# FPGA_Banks_DDR3.net
KiCad netlist of a schematic drawn in Altium Designer
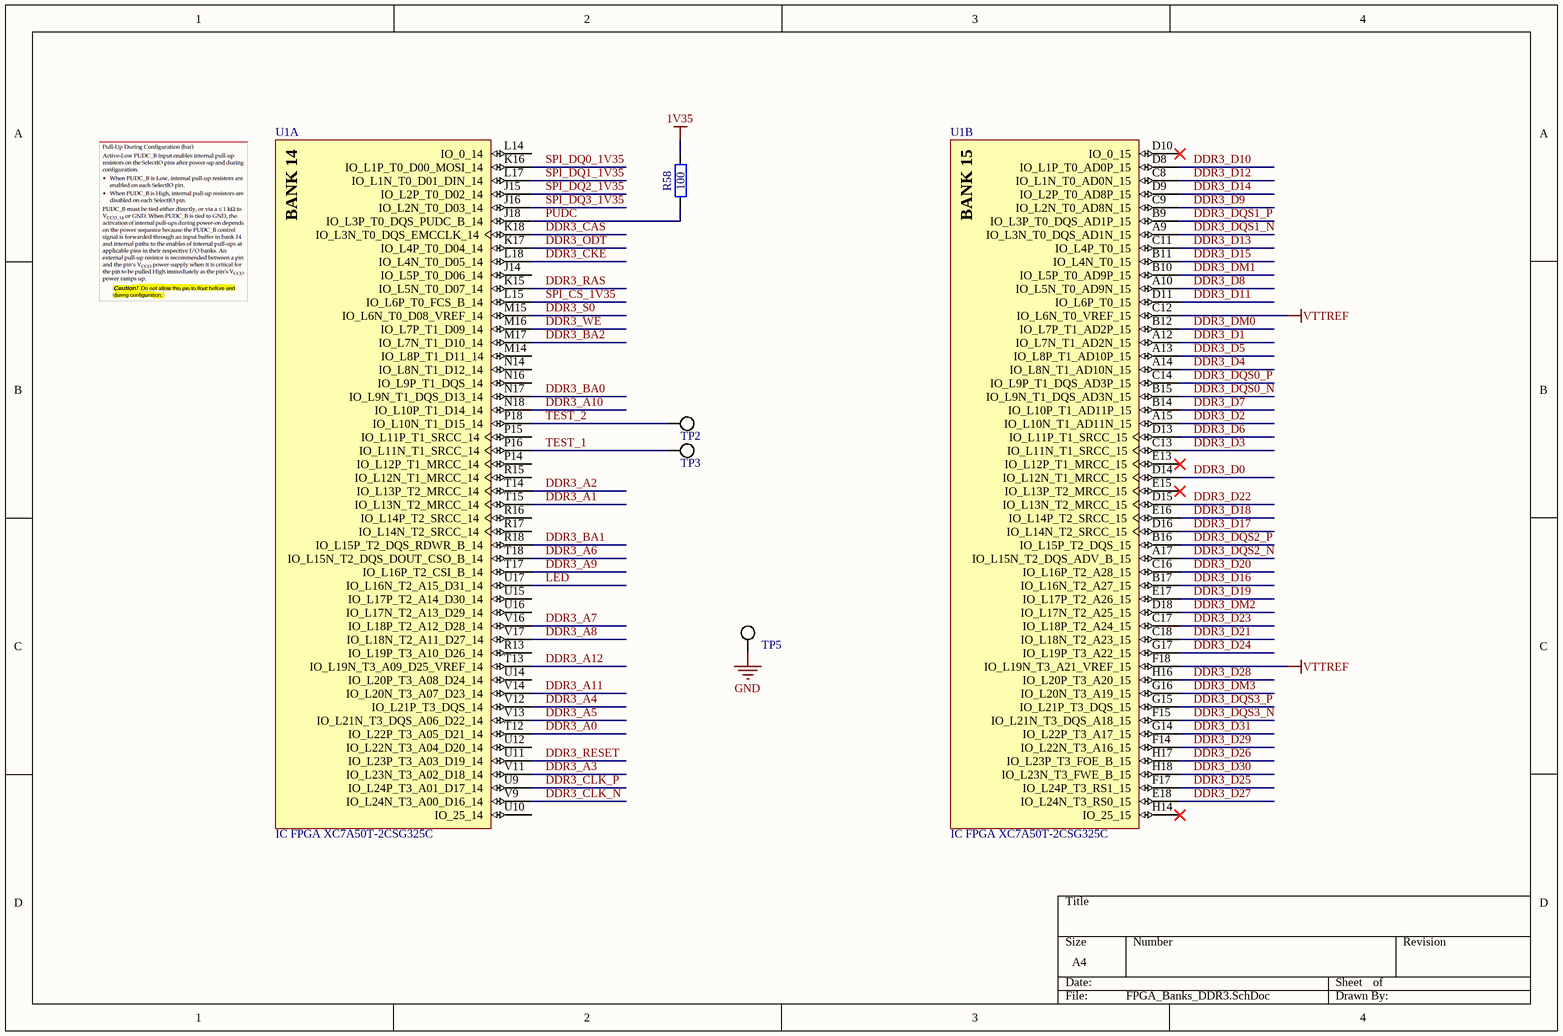
[diagram p0: FPGA_Banks_DDR3.SchDoc]

(export (version "E")
  (design (tool "Eeschema 10.0.6"))
  (components
    (comp (ref "R58")
      (value "100")
      (footprint "GEN_R_0201")
      (fields (field (name "TOLERANCE") "1%"))
      (libsource (lib "DSO") (part "RES 100 OHM 1% 1/20W 0201"))
    )
    (comp (ref "TP2") (value "PCB") (footprint "GEN_TP_PCB") (libsource (lib "DSO") (part "TP PCB 1mm")))
    (comp (ref "TP3") (value "PCB") (footprint "GEN_TP_PCB") (libsource (lib "DSO") (part "TP PCB 1mm")))
    (comp (ref "TP5") (value "PCB") (footprint "GEN_TP_PCB") (libsource (lib "DSO") (part "TP PCB 1mm")))
    (comp (ref "U1")
      (value "IC FPGA XC7A50T-2CSG325C")
      (footprint "XILINX_XC7A50T-2CSG325C")
      (description "Artix-7 FPGA, 150 User I/Os, 4 GTP, 324-Ball BGA, Speed Grade 2, Commercial Grade, Pb-Free")
      (fields (field (name "MANUFACTURER") "Xilinx") (field (name "PARTNUMBER") "XC7A35T-2CSG325C"))
      (libsource (lib "DSO") (part "IC FPGA XC7A50T-2CSG325C"))
    )
  )
  (nets
    (net (code "1") (name "/DDR3_A0") (class "Default")
      (node (ref "U1") (pin "T12") (pinfunction "IO_L22P_T3_A05_D21_14_T12") (pintype "bidirectional"))
    )
    (net (code "2") (name "/DDR3_A1") (class "Default")
      (node (ref "U1") (pin "T15") (pinfunction "IO_L13N_T2_MRCC_14_T15") (pintype "bidirectional"))
    )
    (net (code "3") (name "/DDR3_A2") (class "Default")
      (node (ref "U1") (pin "T14") (pinfunction "IO_L13P_T2_MRCC_14_T14") (pintype "bidirectional"))
    )
    (net (code "4") (name "/DDR3_A3") (class "Default")
      (node (ref "U1") (pin "V11") (pinfunction "IO_L23N_T3_A02_D18_14_V11") (pintype "bidirectional"))
    )
    (net (code "5") (name "/DDR3_A4") (class "Default")
      (node (ref "U1") (pin "V12") (pinfunction "IO_L21P_T3_DQS_14_V12") (pintype "bidirectional"))
    )
    (net (code "6") (name "/DDR3_A5") (class "Default")
      (node (ref "U1") (pin "V13") (pinfunction "IO_L21N_T3_DQS_A06_D22_14_V13") (pintype "bidirectional"))
    )
    (net (code "7") (name "/DDR3_A6") (class "Default")
      (node (ref "U1") (pin "T18") (pinfunction "IO_L15N_T2_DQS_DOUT_CSO_B_14_T18") (pintype "bidirectional"))
    )
    (net (code "8") (name "/DDR3_A7") (class "Default")
      (node (ref "U1") (pin "V16") (pinfunction "IO_L18P_T2_A12_D28_14_V16") (pintype "bidirectional"))
    )
    (net (code "9") (name "/DDR3_A8") (class "Default")
      (node (ref "U1") (pin "V17") (pinfunction "IO_L18N_T2_A11_D27_14_V17") (pintype "bidirectional"))
    )
    (net (code "10") (name "/DDR3_A9") (class "Default")
      (node (ref "U1") (pin "T17") (pinfunction "IO_L16P_T2_CSI_B_14_T17") (pintype "bidirectional"))
    )
    (net (code "11") (name "/DDR3_A10") (class "Default")
      (node (ref "U1") (pin "N18") (pinfunction "IO_L10P_T1_D14_14_N18") (pintype "bidirectional"))
    )
    (net (code "12") (name "/DDR3_A11") (class "Default")
      (node (ref "U1") (pin "V14") (pinfunction "IO_L20N_T3_A07_D23_14_V14") (pintype "bidirectional"))
    )
    (net (code "13") (name "/DDR3_A12") (class "Default")
      (node (ref "U1") (pin "T13") (pinfunction "IO_L19N_T3_A09_D25_VREF_14_T13") (pintype "bidirectional"))
    )
    (net (code "14") (name "/DDR3_BA0") (class "Default")
      (node (ref "U1") (pin "N17") (pinfunction "IO_L9N_T1_DQS_D13_14_N17") (pintype "bidirectional"))
    )
    (net (code "15") (name "/DDR3_BA1") (class "Default")
      (node (ref "U1") (pin "R18") (pinfunction "IO_L15P_T2_DQS_RDWR_B_14_R18") (pintype "bidirectional"))
    )
    (net (code "16") (name "/DDR3_BA2") (class "Default")
      (node (ref "U1") (pin "M17") (pinfunction "IO_L7N_T1_D10_14_M17") (pintype "bidirectional"))
    )
    (net (code "17") (name "/DDR3_CAS") (class "Default")
      (node (ref "U1") (pin "K18") (pinfunction "IO_L3N_T0_DQS_EMCCLK_14_K18") (pintype "bidirectional"))
    )
    (net (code "18") (name "/DDR3_CKE") (class "Default")
      (node (ref "U1") (pin "L18") (pinfunction "IO_L4N_T0_D05_14_L18") (pintype "bidirectional"))
    )
    (net (code "19") (name "/DDR3_CLK_N") (class "Default")
      (node (ref "U1") (pin "V9") (pinfunction "IO_L24N_T3_A00_D16_14_V9") (pintype "bidirectional"))
    )
    (net (code "20") (name "/DDR3_CLK_P") (class "Default")
      (node (ref "U1") (pin "U9") (pinfunction "IO_L24P_T3_A01_D17_14_U9") (pintype "bidirectional"))
    )
    (net (code "21") (name "/DDR3_D0") (class "Default")
      (node (ref "U1") (pin "D14") (pinfunction "IO_L12N_T1_MRCC_15_D14") (pintype "bidirectional"))
    )
    (net (code "22") (name "/DDR3_D1") (class "Default")
      (node (ref "U1") (pin "A12") (pinfunction "IO_L7N_T1_AD2N_15_A12") (pintype "bidirectional"))
    )
    (net (code "23") (name "/DDR3_D2") (class "Default")
      (node (ref "U1") (pin "A15") (pinfunction "IO_L10N_T1_AD11N_15_A15") (pintype "bidirectional"))
    )
    (net (code "24") (name "/DDR3_D3") (class "Default")
      (node (ref "U1") (pin "C13") (pinfunction "IO_L11N_T1_SRCC_15_C13") (pintype "bidirectional"))
    )
    (net (code "25") (name "/DDR3_D4") (class "Default")
      (node (ref "U1") (pin "A14") (pinfunction "IO_L8N_T1_AD10N_15_A14") (pintype "bidirectional"))
    )
    (net (code "26") (name "/DDR3_D5") (class "Default")
      (node (ref "U1") (pin "A13") (pinfunction "IO_L8P_T1_AD10P_15_A13") (pintype "bidirectional"))
    )
    (net (code "27") (name "/DDR3_D6") (class "Default")
      (node (ref "U1") (pin "D13") (pinfunction "IO_L11P_T1_SRCC_15_D13") (pintype "bidirectional"))
    )
    (net (code "28") (name "/DDR3_D7") (class "Default")
      (node (ref "U1") (pin "B14") (pinfunction "IO_L10P_T1_AD11P_15_B14") (pintype "bidirectional"))
    )
    (net (code "29") (name "/DDR3_D8") (class "Default")
      (node (ref "U1") (pin "A10") (pinfunction "IO_L5N_T0_AD9N_15_A10") (pintype "bidirectional"))
    )
    (net (code "30") (name "/DDR3_D9") (class "Default")
      (node (ref "U1") (pin "C9") (pinfunction "IO_L2N_T0_AD8N_15_C9") (pintype "bidirectional"))
    )
    (net (code "31") (name "/DDR3_D10") (class "Default")
      (node (ref "U1") (pin "D8") (pinfunction "IO_L1P_T0_AD0P_15_D8") (pintype "bidirectional"))
    )
    (net (code "32") (name "/DDR3_D11") (class "Default")
      (node (ref "U1") (pin "D11") (pinfunction "IO_L6P_T0_15_D11") (pintype "bidirectional"))
    )
    (net (code "33") (name "/DDR3_D12") (class "Default")
      (node (ref "U1") (pin "C8") (pinfunction "IO_L1N_T0_AD0N_15_C8") (pintype "bidirectional"))
    )
    (net (code "34") (name "/DDR3_D13") (class "Default")
      (node (ref "U1") (pin "C11") (pinfunction "IO_L4P_T0_15_C11") (pintype "bidirectional"))
    )
    (net (code "35") (name "/DDR3_D14") (class "Default")
      (node (ref "U1") (pin "D9") (pinfunction "IO_L2P_T0_AD8P_15_D9") (pintype "bidirectional"))
    )
    (net (code "36") (name "/DDR3_D15") (class "Default")
      (node (ref "U1") (pin "B11") (pinfunction "IO_L4N_T0_15_B11") (pintype "bidirectional"))
    )
    (net (code "37") (name "/DDR3_D16") (class "Default")
      (node (ref "U1") (pin "B17") (pinfunction "IO_L16N_T2_A27_15_B17") (pintype "bidirectional"))
    )
    (net (code "38") (name "/DDR3_D17") (class "Default")
      (node (ref "U1") (pin "D16") (pinfunction "IO_L14N_T2_SRCC_15_D16") (pintype "bidirectional"))
    )
    (net (code "39") (name "/DDR3_D18") (class "Default")
      (node (ref "U1") (pin "E16") (pinfunction "IO_L14P_T2_SRCC_15_E16") (pintype "bidirectional"))
    )
    (net (code "40") (name "/DDR3_D19") (class "Default")
      (node (ref "U1") (pin "E17") (pinfunction "IO_L17P_T2_A26_15_E17") (pintype "bidirectional"))
    )
    (net (code "41") (name "/DDR3_D20") (class "Default")
      (node (ref "U1") (pin "C16") (pinfunction "IO_L16P_T2_A28_15_C16") (pintype "bidirectional"))
    )
    (net (code "42") (name "/DDR3_D21") (class "Default")
      (node (ref "U1") (pin "C18") (pinfunction "IO_L18N_T2_A23_15_C18") (pintype "bidirectional"))
    )
    (net (code "43") (name "/DDR3_D22") (class "Default")
      (node (ref "U1") (pin "D15") (pinfunction "IO_L13N_T2_MRCC_15_D15") (pintype "bidirectional"))
    )
    (net (code "44") (name "/DDR3_D23") (class "Default")
      (node (ref "U1") (pin "C17") (pinfunction "IO_L18P_T2_A24_15_C17") (pintype "bidirectional"))
    )
    (net (code "45") (name "/DDR3_D24") (class "Default")
      (node (ref "U1") (pin "G17") (pinfunction "IO_L19P_T3_A22_15_G17") (pintype "bidirectional"))
    )
    (net (code "46") (name "/DDR3_D25") (class "Default")
      (node (ref "U1") (pin "F17") (pinfunction "IO_L24P_T3_RS1_15_F17") (pintype "bidirectional"))
    )
    (net (code "47") (name "/DDR3_D26") (class "Default")
      (node (ref "U1") (pin "H17") (pinfunction "IO_L23P_T3_FOE_B_15_H17") (pintype "bidirectional"))
    )
    (net (code "48") (name "/DDR3_D27") (class "Default")
      (node (ref "U1") (pin "E18") (pinfunction "IO_L24N_T3_RS0_15_E18") (pintype "bidirectional"))
    )
    (net (code "49") (name "/DDR3_D28") (class "Default")
      (node (ref "U1") (pin "H16") (pinfunction "IO_L20P_T3_A20_15_H16") (pintype "bidirectional"))
    )
    (net (code "50") (name "/DDR3_D29") (class "Default")
      (node (ref "U1") (pin "F14") (pinfunction "IO_L22N_T3_A16_15_F14") (pintype "bidirectional"))
    )
    (net (code "51") (name "/DDR3_D30") (class "Default")
      (node (ref "U1") (pin "H18") (pinfunction "IO_L23N_T3_FWE_B_15_H18") (pintype "bidirectional"))
    )
    (net (code "52") (name "/DDR3_D31") (class "Default")
      (node (ref "U1") (pin "G14") (pinfunction "IO_L22P_T3_A17_15_G14") (pintype "bidirectional"))
    )
    (net (code "53") (name "/DDR3_DM0") (class "Default")
      (node (ref "U1") (pin "B12") (pinfunction "IO_L7P_T1_AD2P_15_B12") (pintype "bidirectional"))
    )
    (net (code "54") (name "/DDR3_DM1") (class "Default")
      (node (ref "U1") (pin "B10") (pinfunction "IO_L5P_T0_AD9P_15_B10") (pintype "bidirectional"))
    )
    (net (code "55") (name "/DDR3_DM2") (class "Default")
      (node (ref "U1") (pin "D18") (pinfunction "IO_L17N_T2_A25_15_D18") (pintype "bidirectional"))
    )
    (net (code "56") (name "/DDR3_DM3") (class "Default")
      (node (ref "U1") (pin "G16") (pinfunction "IO_L20N_T3_A19_15_G16") (pintype "bidirectional"))
    )
    (net (code "57") (name "/DDR3_DQS0_N") (class "Default")
      (node (ref "U1") (pin "B15") (pinfunction "IO_L9N_T1_DQS_AD3N_15_B15") (pintype "bidirectional"))
    )
    (net (code "58") (name "/DDR3_DQS0_P") (class "Default")
      (node (ref "U1") (pin "C14") (pinfunction "IO_L9P_T1_DQS_AD3P_15_C14") (pintype "bidirectional"))
    )
    (net (code "59") (name "/DDR3_DQS1_N") (class "Default")
      (node (ref "U1") (pin "A9") (pinfunction "IO_L3N_T0_DQS_AD1N_15_A9") (pintype "bidirectional"))
    )
    (net (code "60") (name "/DDR3_DQS1_P") (class "Default")
      (node (ref "U1") (pin "B9") (pinfunction "IO_L3P_T0_DQS_AD1P_15_B9") (pintype "bidirectional"))
    )
    (net (code "61") (name "/DDR3_DQS2_N") (class "Default")
      (node (ref "U1") (pin "A17") (pinfunction "IO_L15N_T2_DQS_ADV_B_15_A17") (pintype "bidirectional"))
    )
    (net (code "62") (name "/DDR3_DQS2_P") (class "Default")
      (node (ref "U1") (pin "B16") (pinfunction "IO_L15P_T2_DQS_15_B16") (pintype "bidirectional"))
    )
    (net (code "63") (name "/DDR3_DQS3_N") (class "Default")
      (node (ref "U1") (pin "F15") (pinfunction "IO_L21N_T3_DQS_A18_15_F15") (pintype "bidirectional"))
    )
    (net (code "64") (name "/DDR3_DQS3_P") (class "Default")
      (node (ref "U1") (pin "G15") (pinfunction "IO_L21P_T3_DQS_15_G15") (pintype "bidirectional"))
    )
    (net (code "65") (name "/DDR3_ODT") (class "Default")
      (node (ref "U1") (pin "K17") (pinfunction "IO_L4P_T0_D04_14_K17") (pintype "bidirectional"))
    )
    (net (code "66") (name "/DDR3_RAS") (class "Default")
      (node (ref "U1") (pin "K15") (pinfunction "IO_L5N_T0_D07_14_K15") (pintype "bidirectional"))
    )
    (net (code "67") (name "/DDR3_RESET") (class "Default")
      (node (ref "U1") (pin "U11") (pinfunction "IO_L23P_T3_A03_D19_14_U11") (pintype "bidirectional"))
    )
    (net (code "68") (name "/DDR3_S0") (class "Default")
      (node (ref "U1") (pin "M15") (pinfunction "IO_L6N_T0_D08_VREF_14_M15") (pintype "bidirectional"))
    )
    (net (code "69") (name "/DDR3_WE") (class "Default")
      (node (ref "U1") (pin "M16") (pinfunction "IO_L7P_T1_D09_14_M16") (pintype "bidirectional"))
    )
    (net (code "70") (name "/LED") (class "Default")
      (node (ref "U1") (pin "U17") (pinfunction "IO_L16N_T2_A15_D31_14_U17") (pintype "bidirectional"))
    )
    (net (code "71") (name "/PUDC") (class "Default")
      (node (ref "R58") (pin "1") (pinfunction "1_1") (pintype "passive"))
      (node (ref "U1") (pin "J18") (pinfunction "IO_L3P_T0_DQS_PUDC_B_14_J18") (pintype "bidirectional"))
    )
    (net (code "72") (name "/SPI_CS_1V35") (class "Default")
      (node (ref "U1") (pin "L15") (pinfunction "IO_L6P_T0_FCS_B_14_L15") (pintype "bidirectional"))
    )
    (net (code "73") (name "/SPI_DQ0_1V35") (class "Default")
      (node (ref "U1") (pin "K16") (pinfunction "IO_L1P_T0_D00_MOSI_14_K16") (pintype "bidirectional"))
    )
    (net (code "74") (name "/SPI_DQ1_1V35") (class "Default")
      (node (ref "U1") (pin "L17") (pinfunction "IO_L1N_T0_D01_DIN_14_L17") (pintype "bidirectional"))
    )
    (net (code "75") (name "/SPI_DQ2_1V35") (class "Default")
      (node (ref "U1") (pin "J15") (pinfunction "IO_L2P_T0_D02_14_J15") (pintype "bidirectional"))
    )
    (net (code "76") (name "/SPI_DQ3_1V35") (class "Default")
      (node (ref "U1") (pin "J16") (pinfunction "IO_L2N_T0_D03_14_J16") (pintype "bidirectional"))
    )
    (net (code "77") (name "/TEST_1") (class "Default")
      (node (ref "TP3") (pin "1") (pinfunction "1_1") (pintype "passive"))
      (node (ref "U1") (pin "P16") (pinfunction "IO_L11N_T1_SRCC_14_P16") (pintype "bidirectional"))
    )
    (net (code "78") (name "/TEST_2") (class "Default")
      (node (ref "TP2") (pin "1") (pinfunction "1_1") (pintype "passive"))
      (node (ref "U1") (pin "P18") (pinfunction "IO_L10N_T1_D15_14_P18") (pintype "bidirectional"))
    )
    (net (code "79") (name "1V35") (class "Default")
      (node (ref "R58") (pin "2") (pinfunction "2_2") (pintype "passive"))
    )
    (net (code "80") (name "GND") (class "Default")
      (node (ref "TP5") (pin "1") (pinfunction "1_1") (pintype "passive"))
    )
    (net (code "81") (name "VTTREF") (class "Default")
      (node (ref "U1") (pin "C12") (pinfunction "IO_L6N_T0_VREF_15_C12") (pintype "bidirectional"))
      (node (ref "U1") (pin "F18") (pinfunction "IO_L19N_T3_A21_VREF_15_F18") (pintype "bidirectional"))
    )
    (net (code "82") (name "unconnected-(U1A-IO_0_14-PadL14)") (class "Default")
      (node (ref "U1") (pin "L14") (pinfunction "IO_0_14_L14") (pintype "bidirectional"))
    )
    (net (code "83") (name "unconnected-(U1A-IO_25_14-PadU10)") (class "Default")
      (node (ref "U1") (pin "U10") (pinfunction "IO_25_14_U10") (pintype "bidirectional"))
    )
    (net (code "84") (name "unconnected-(U1A-IO_L5P_T0_D06_14-PadJ14)") (class "Default")
      (node (ref "U1") (pin "J14") (pinfunction "IO_L5P_T0_D06_14_J14") (pintype "bidirectional"))
    )
    (net (code "85") (name "unconnected-(U1A-IO_L8N_T1_D12_14-PadN14)") (class "Default")
      (node (ref "U1") (pin "N14") (pinfunction "IO_L8N_T1_D12_14_N14") (pintype "bidirectional"))
    )
    (net (code "86") (name "unconnected-(U1A-IO_L8P_T1_D11_14-PadM14)") (class "Default")
      (node (ref "U1") (pin "M14") (pinfunction "IO_L8P_T1_D11_14_M14") (pintype "bidirectional"))
    )
    (net (code "87") (name "unconnected-(U1A-IO_L9P_T1_DQS_14-PadN16)") (class "Default")
      (node (ref "U1") (pin "N16") (pinfunction "IO_L9P_T1_DQS_14_N16") (pintype "bidirectional"))
    )
    (net (code "88") (name "unconnected-(U1A-IO_L11P_T1_SRCC_14-PadP15)") (class "Default")
      (node (ref "U1") (pin "P15") (pinfunction "IO_L11P_T1_SRCC_14_P15") (pintype "bidirectional"))
    )
    (net (code "89") (name "unconnected-(U1A-IO_L12N_T1_MRCC_14-PadR15)") (class "Default")
      (node (ref "U1") (pin "R15") (pinfunction "IO_L12N_T1_MRCC_14_R15") (pintype "bidirectional"))
    )
    (net (code "90") (name "unconnected-(U1A-IO_L12P_T1_MRCC_14-PadP14)") (class "Default")
      (node (ref "U1") (pin "P14") (pinfunction "IO_L12P_T1_MRCC_14_P14") (pintype "bidirectional"))
    )
    (net (code "91") (name "unconnected-(U1A-IO_L14N_T2_SRCC_14-PadR17)") (class "Default")
      (node (ref "U1") (pin "R17") (pinfunction "IO_L14N_T2_SRCC_14_R17") (pintype "bidirectional"))
    )
    (net (code "92") (name "unconnected-(U1A-IO_L14P_T2_SRCC_14-PadR16)") (class "Default")
      (node (ref "U1") (pin "R16") (pinfunction "IO_L14P_T2_SRCC_14_R16") (pintype "bidirectional"))
    )
    (net (code "93") (name "unconnected-(U1A-IO_L17N_T2_A13_D29_14-PadU16)") (class "Default")
      (node (ref "U1") (pin "U16") (pinfunction "IO_L17N_T2_A13_D29_14_U16") (pintype "bidirectional"))
    )
    (net (code "94") (name "unconnected-(U1A-IO_L17P_T2_A14_D30_14-PadU15)") (class "Default")
      (node (ref "U1") (pin "U15") (pinfunction "IO_L17P_T2_A14_D30_14_U15") (pintype "bidirectional"))
    )
    (net (code "95") (name "unconnected-(U1A-IO_L19P_T3_A10_D26_14-PadR13)") (class "Default")
      (node (ref "U1") (pin "R13") (pinfunction "IO_L19P_T3_A10_D26_14_R13") (pintype "bidirectional"))
    )
    (net (code "96") (name "unconnected-(U1A-IO_L20P_T3_A08_D24_14-PadU14)") (class "Default")
      (node (ref "U1") (pin "U14") (pinfunction "IO_L20P_T3_A08_D24_14_U14") (pintype "bidirectional"))
    )
    (net (code "97") (name "unconnected-(U1A-IO_L22N_T3_A04_D20_14-PadU12)") (class "Default")
      (node (ref "U1") (pin "U12") (pinfunction "IO_L22N_T3_A04_D20_14_U12") (pintype "bidirectional"))
    )
    (net (code "98") (name "unconnected-(U1B-IO_0_15-PadD10)") (class "Default")
      (node (ref "U1") (pin "D10") (pinfunction "IO_0_15_D10") (pintype "bidirectional+no_connect"))
    )
    (net (code "99") (name "unconnected-(U1B-IO_25_15-PadH14)") (class "Default")
      (node (ref "U1") (pin "H14") (pinfunction "IO_25_15_H14") (pintype "bidirectional+no_connect"))
    )
    (net (code "100") (name "unconnected-(U1B-IO_L12P_T1_MRCC_15-PadE13)") (class "Default")
      (node (ref "U1") (pin "E13") (pinfunction "IO_L12P_T1_MRCC_15_E13") (pintype "bidirectional+no_connect"))
    )
    (net (code "101") (name "unconnected-(U1B-IO_L13P_T2_MRCC_15-PadE15)") (class "Default")
      (node (ref "U1") (pin "E15") (pinfunction "IO_L13P_T2_MRCC_15_E15") (pintype "bidirectional+no_connect"))
    )
  )
)
